# main.net
KiCad netlist of a schematic drawn in Altium Designer
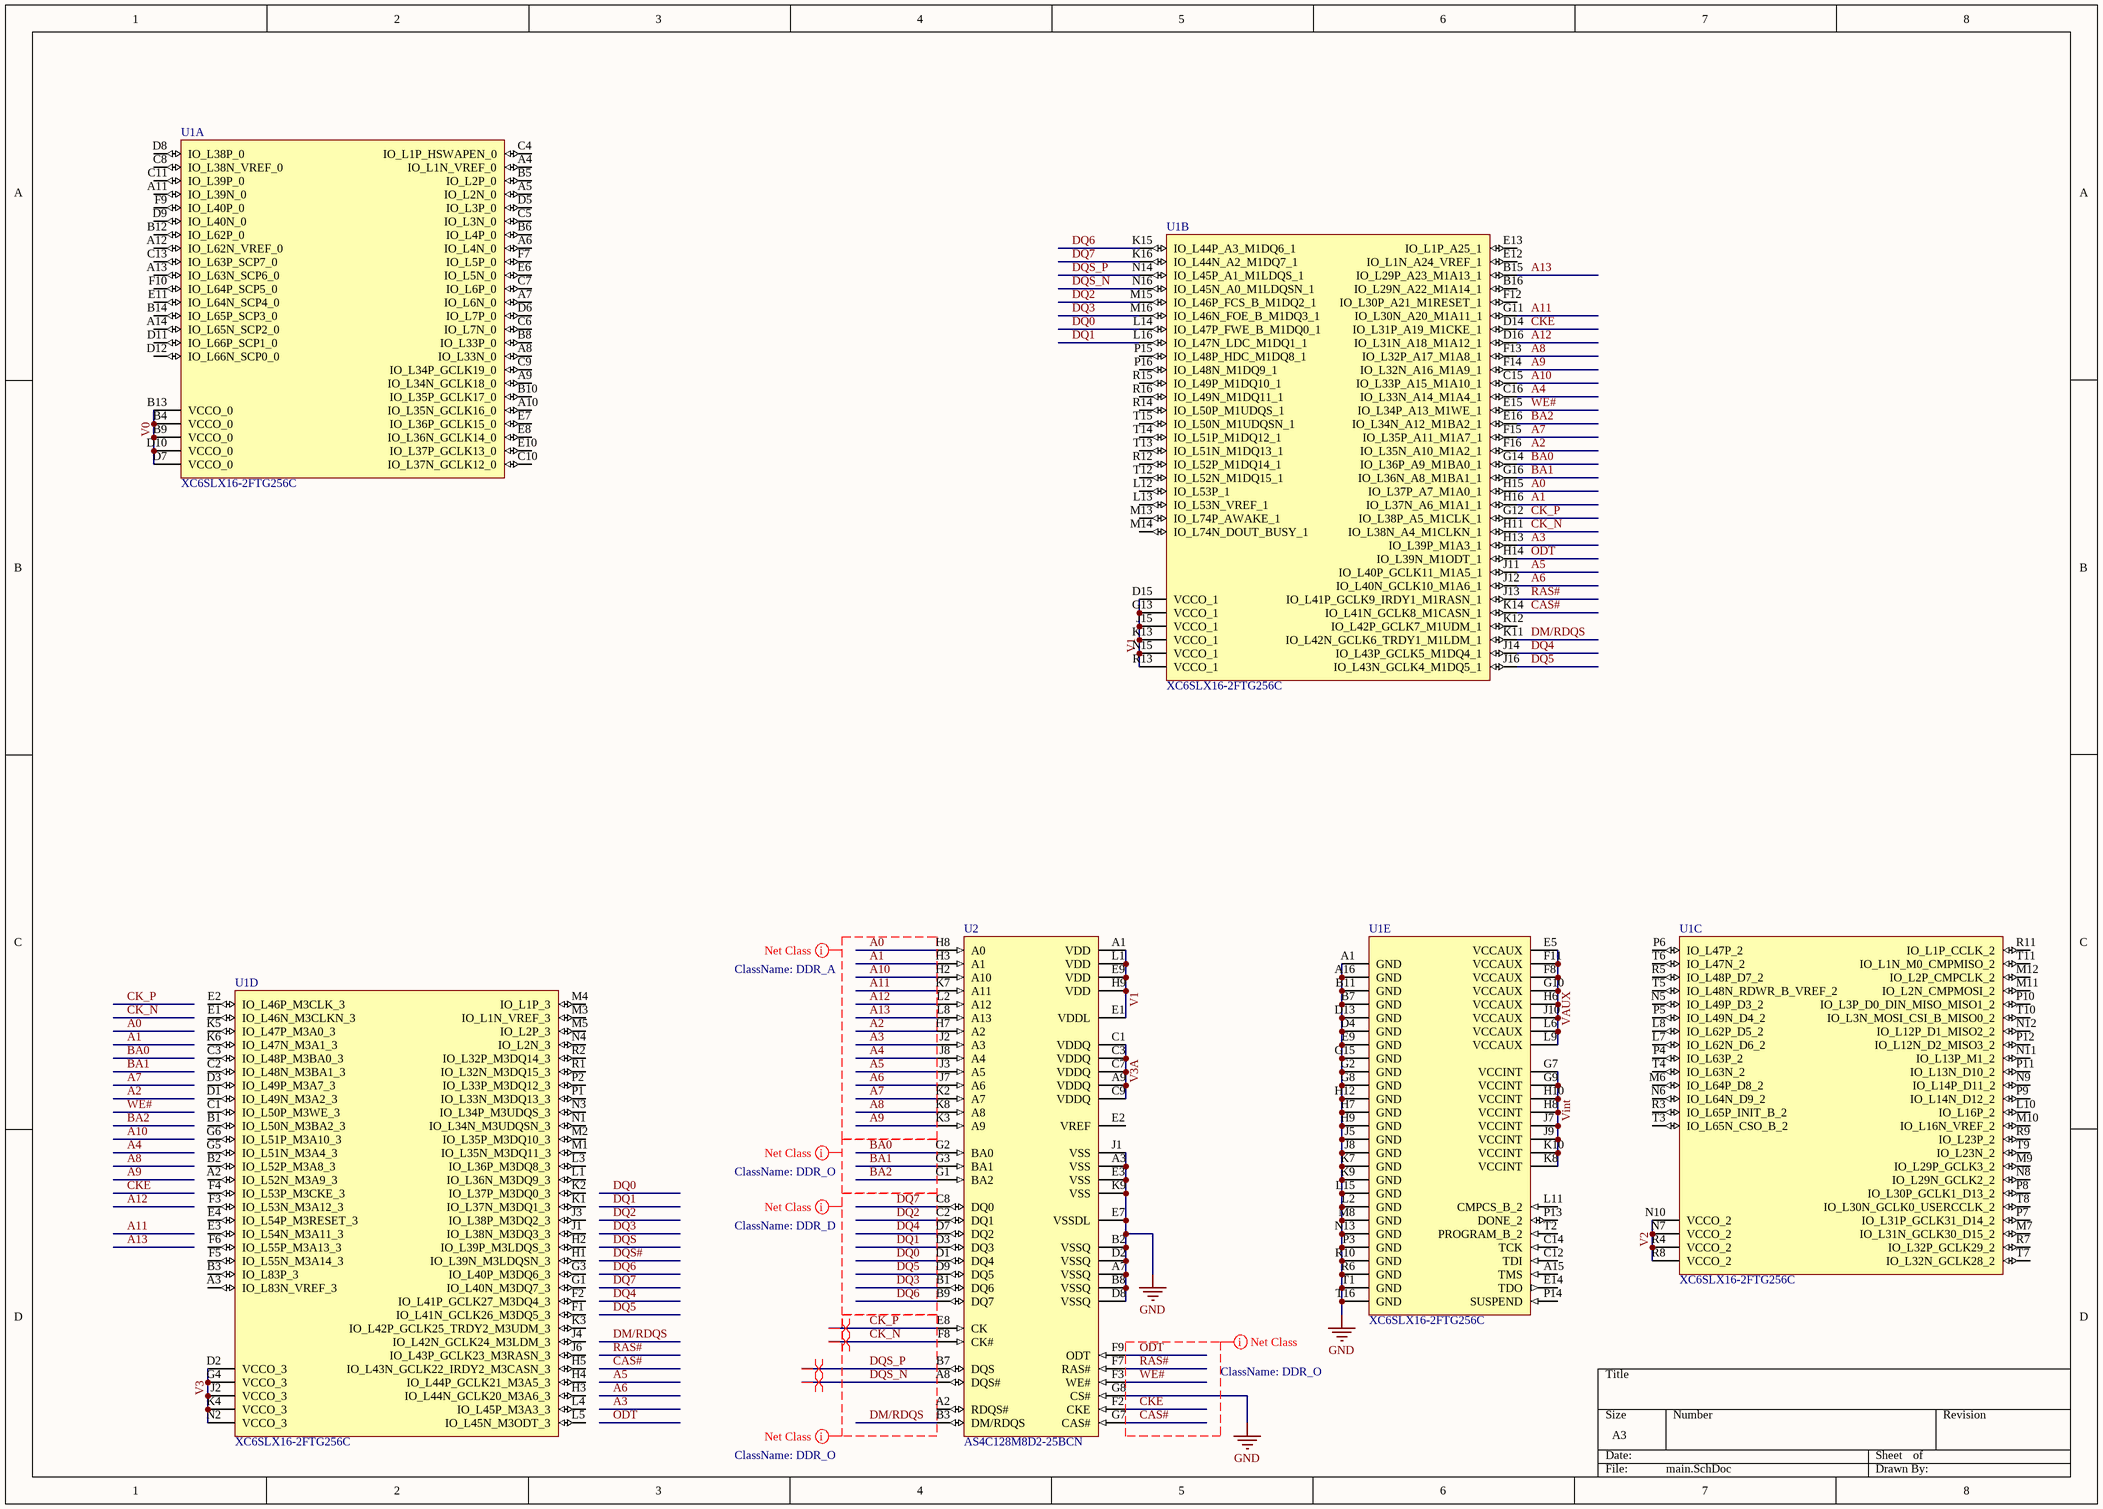
[diagram p0: main.SchDoc]

(export (version "E")
  (design (tool "Eeschema 10.0.6"))
  (components
    (comp (ref "U1")
      (value "XC6SLX16-2FTG256C")
      (footprint "Xilinx_FT256")
      (libsource (lib "niceCircuits") (part "XC6SLX16-2FTG256C"))
    )
    (comp (ref "U2")
      (value "AS4C128M8D2-25BCN")
      (footprint "Alliance_FBGA60")
      (libsource (lib "niceCircuits") (part "AS4C128M8D2-25BCN"))
    )
  )
  (nets
    (net (code "1") (name "/A0") (class "Default")
      (node (ref "U1") (pin "H15") (pinfunction "IO_L37P_A7_M1A0_1_H15") (pintype "bidirectional"))
      (node (ref "U2") (pin "H8") (pinfunction "A0_H8") (pintype "input"))
    )
    (net (code "2") (name "/A1") (class "Default")
      (node (ref "U1") (pin "H16") (pinfunction "IO_L37N_A6_M1A1_1_H16") (pintype "bidirectional"))
      (node (ref "U2") (pin "H3") (pinfunction "A1_H3") (pintype "input"))
    )
    (net (code "3") (name "/A2") (class "Default")
      (node (ref "U1") (pin "F16") (pinfunction "IO_L35N_A10_M1A2_1_F16") (pintype "bidirectional"))
      (node (ref "U2") (pin "H7") (pinfunction "A2_H7") (pintype "input"))
    )
    (net (code "4") (name "/A3") (class "Default")
      (node (ref "U1") (pin "H13") (pinfunction "IO_L39P_M1A3_1_H13") (pintype "bidirectional"))
      (node (ref "U2") (pin "J2") (pinfunction "A3_J2") (pintype "input"))
    )
    (net (code "5") (name "/A4") (class "Default")
      (node (ref "U1") (pin "C16") (pinfunction "IO_L33N_A14_M1A4_1_C16") (pintype "bidirectional"))
      (node (ref "U2") (pin "J8") (pinfunction "A4_J8") (pintype "input"))
    )
    (net (code "6") (name "/A5") (class "Default")
      (node (ref "U1") (pin "J11") (pinfunction "IO_L40P_GCLK11_M1A5_1_J11") (pintype "bidirectional"))
      (node (ref "U2") (pin "J3") (pinfunction "A5_J3") (pintype "input"))
    )
    (net (code "7") (name "/A6") (class "Default")
      (node (ref "U1") (pin "J12") (pinfunction "IO_L40N_GCLK10_M1A6_1_J12") (pintype "bidirectional"))
      (node (ref "U2") (pin "J7") (pinfunction "A6_J7") (pintype "input"))
    )
    (net (code "8") (name "/A7") (class "Default")
      (node (ref "U1") (pin "F15") (pinfunction "IO_L35P_A11_M1A7_1_F15") (pintype "bidirectional"))
      (node (ref "U2") (pin "K2") (pinfunction "A7_K2") (pintype "input"))
    )
    (net (code "9") (name "/A8") (class "Default")
      (node (ref "U1") (pin "F13") (pinfunction "IO_L32P_A17_M1A8_1_F13") (pintype "bidirectional"))
      (node (ref "U2") (pin "K8") (pinfunction "A8_K8") (pintype "input"))
    )
    (net (code "10") (name "/A9") (class "Default")
      (node (ref "U1") (pin "F14") (pinfunction "IO_L32N_A16_M1A9_1_F14") (pintype "bidirectional"))
      (node (ref "U2") (pin "K3") (pinfunction "A9_K3") (pintype "input"))
    )
    (net (code "11") (name "/A10") (class "Default")
      (node (ref "U1") (pin "C15") (pinfunction "IO_L33P_A15_M1A10_1_C15") (pintype "bidirectional"))
      (node (ref "U2") (pin "H2") (pinfunction "A10_H2") (pintype "input"))
    )
    (net (code "12") (name "/A11") (class "Default")
      (node (ref "U1") (pin "G11") (pinfunction "IO_L30N_A20_M1A11_1_G11") (pintype "bidirectional"))
      (node (ref "U2") (pin "K7") (pinfunction "A11_K7") (pintype "input"))
    )
    (net (code "13") (name "/A12") (class "Default")
      (node (ref "U1") (pin "D16") (pinfunction "IO_L31N_A18_M1A12_1_D16") (pintype "bidirectional"))
      (node (ref "U2") (pin "L2") (pinfunction "A12_L2") (pintype "input"))
    )
    (net (code "14") (name "/A13") (class "Default")
      (node (ref "U1") (pin "B15") (pinfunction "IO_L29P_A23_M1A13_1_B15") (pintype "bidirectional"))
      (node (ref "U2") (pin "L8") (pinfunction "A13_L8") (pintype "input"))
    )
    (net (code "15") (name "/BA0") (class "Default")
      (node (ref "U1") (pin "G14") (pinfunction "IO_L36P_A9_M1BA0_1_G14") (pintype "bidirectional"))
      (node (ref "U2") (pin "G2") (pinfunction "BA0_G2") (pintype "input"))
    )
    (net (code "16") (name "/BA1") (class "Default")
      (node (ref "U1") (pin "G16") (pinfunction "IO_L36N_A8_M1BA1_1_G16") (pintype "bidirectional"))
      (node (ref "U2") (pin "G3") (pinfunction "BA1_G3") (pintype "input"))
    )
    (net (code "17") (name "/BA2") (class "Default")
      (node (ref "U1") (pin "E16") (pinfunction "IO_L34N_A12_M1BA2_1_E16") (pintype "bidirectional"))
      (node (ref "U2") (pin "G1") (pinfunction "BA2_G1") (pintype "input"))
    )
    (net (code "18") (name "/CAS#") (class "Default")
      (node (ref "U1") (pin "K14") (pinfunction "IO_L41N_GCLK8_M1CASN_1_K14") (pintype "bidirectional"))
      (node (ref "U2") (pin "G7") (pinfunction "CAS#_G7") (pintype "input"))
    )
    (net (code "19") (name "/CKE") (class "Default")
      (node (ref "U1") (pin "D14") (pinfunction "IO_L31P_A19_M1CKE_1_D14") (pintype "bidirectional"))
      (node (ref "U2") (pin "F2") (pinfunction "CKE_F2") (pintype "input"))
    )
    (net (code "20") (name "/CK_N") (class "Default")
      (node (ref "U1") (pin "H11") (pinfunction "IO_L38N_A4_M1CLKN_1_H11") (pintype "bidirectional"))
      (node (ref "U2") (pin "F8") (pinfunction "CK#_F8") (pintype "input"))
    )
    (net (code "21") (name "/CK_P") (class "Default")
      (node (ref "U1") (pin "G12") (pinfunction "IO_L38P_A5_M1CLK_1_G12") (pintype "bidirectional"))
      (node (ref "U2") (pin "E8") (pinfunction "CK_E8") (pintype "input"))
    )
    (net (code "22") (name "/DM{slash}RDQS") (class "Default")
      (node (ref "U1") (pin "K11") (pinfunction "IO_L42N_GCLK6_TRDY1_M1LDM_1_K11") (pintype "bidirectional"))
      (node (ref "U2") (pin "B3") (pinfunction "DM/RDQS_B3") (pintype "bidirectional"))
    )
    (net (code "23") (name "/DQ0") (class "Default")
      (node (ref "U1") (pin "L14") (pinfunction "IO_L47P_FWE_B_M1DQ0_1_L14") (pintype "bidirectional"))
      (node (ref "U2") (pin "D1") (pinfunction "DQ4_D1") (pintype "bidirectional"))
    )
    (net (code "24") (name "/DQ1") (class "Default")
      (node (ref "U1") (pin "L16") (pinfunction "IO_L47N_LDC_M1DQ1_1_L16") (pintype "bidirectional"))
      (node (ref "U2") (pin "D3") (pinfunction "DQ3_D3") (pintype "bidirectional"))
    )
    (net (code "25") (name "/DQ2") (class "Default")
      (node (ref "U1") (pin "M15") (pinfunction "IO_L46P_FCS_B_M1DQ2_1_M15") (pintype "bidirectional"))
      (node (ref "U2") (pin "C2") (pinfunction "DQ1_C2") (pintype "bidirectional"))
    )
    (net (code "26") (name "/DQ3") (class "Default")
      (node (ref "U1") (pin "M16") (pinfunction "IO_L46N_FOE_B_M1DQ3_1_M16") (pintype "bidirectional"))
      (node (ref "U2") (pin "B1") (pinfunction "DQ6_B1") (pintype "bidirectional"))
    )
    (net (code "27") (name "/DQ4") (class "Default")
      (node (ref "U1") (pin "J14") (pinfunction "IO_L43P_GCLK5_M1DQ4_1_J14") (pintype "bidirectional"))
      (node (ref "U2") (pin "D7") (pinfunction "DQ2_D7") (pintype "bidirectional"))
    )
    (net (code "28") (name "/DQ5") (class "Default")
      (node (ref "U1") (pin "J16") (pinfunction "IO_L43N_GCLK4_M1DQ5_1_J16") (pintype "bidirectional"))
      (node (ref "U2") (pin "D9") (pinfunction "DQ5_D9") (pintype "bidirectional"))
    )
    (net (code "29") (name "/DQ6") (class "Default")
      (node (ref "U1") (pin "K15") (pinfunction "IO_L44P_A3_M1DQ6_1_K15") (pintype "bidirectional"))
      (node (ref "U2") (pin "B9") (pinfunction "DQ7_B9") (pintype "bidirectional"))
    )
    (net (code "30") (name "/DQ7") (class "Default")
      (node (ref "U1") (pin "K16") (pinfunction "IO_L44N_A2_M1DQ7_1_K16") (pintype "bidirectional"))
      (node (ref "U2") (pin "C8") (pinfunction "DQ0_C8") (pintype "bidirectional"))
    )
    (net (code "33") (name "/DQS_N") (class "Default")
      (node (ref "U1") (pin "N16") (pinfunction "IO_L45N_A0_M1LDQSN_1_N16") (pintype "bidirectional"))
      (node (ref "U2") (pin "A8") (pinfunction "DQS#_A8") (pintype "bidirectional"))
    )
    (net (code "34") (name "/DQS_P") (class "Default")
      (node (ref "U1") (pin "N14") (pinfunction "IO_L45P_A1_M1LDQS_1_N14") (pintype "bidirectional"))
      (node (ref "U2") (pin "B7") (pinfunction "DQS_B7") (pintype "bidirectional"))
    )
    (net (code "35") (name "/ODT") (class "Default")
      (node (ref "U1") (pin "H14") (pinfunction "IO_L39N_M1ODT_1_H14") (pintype "bidirectional"))
      (node (ref "U2") (pin "F9") (pinfunction "ODT_F9") (pintype "input"))
    )
    (net (code "36") (name "/RAS#") (class "Default")
      (node (ref "U1") (pin "J13") (pinfunction "IO_L41P_GCLK9_IRDY1_M1RASN_1_J13") (pintype "bidirectional"))
      (node (ref "U2") (pin "F7") (pinfunction "RAS#_F7") (pintype "input"))
    )
    (net (code "37") (name "/V0") (class "Default")
      (node (ref "U1") (pin "B13") (pinfunction "VCCO_0_B13") (pintype "power_in"))
      (node (ref "U1") (pin "B4") (pinfunction "VCCO_0_B4") (pintype "power_in"))
      (node (ref "U1") (pin "B9") (pinfunction "VCCO_0_B9") (pintype "power_in"))
      (node (ref "U1") (pin "D10") (pinfunction "VCCO_0_D10") (pintype "power_in"))
      (node (ref "U1") (pin "D7") (pinfunction "VCCO_0_D7") (pintype "power_in"))
    )
    (net (code "38") (name "/V1") (class "Default")
      (node (ref "U1") (pin "D15") (pinfunction "VCCO_1_D15") (pintype "power_in"))
      (node (ref "U1") (pin "G13") (pinfunction "VCCO_1_G13") (pintype "power_in"))
      (node (ref "U1") (pin "J15") (pinfunction "VCCO_1_J15") (pintype "power_in"))
      (node (ref "U1") (pin "K13") (pinfunction "VCCO_1_K13") (pintype "power_in"))
      (node (ref "U1") (pin "N15") (pinfunction "VCCO_1_N15") (pintype "power_in"))
      (node (ref "U1") (pin "R13") (pinfunction "VCCO_1_R13") (pintype "power_in"))
      (node (ref "U2") (pin "A1") (pinfunction "VDD_A1") (pintype "power_in"))
      (node (ref "U2") (pin "E1") (pinfunction "VDDL_E1") (pintype "power_in"))
      (node (ref "U2") (pin "E9") (pinfunction "VDD_E9") (pintype "power_in"))
      (node (ref "U2") (pin "H9") (pinfunction "VDD_H9") (pintype "power_in"))
      (node (ref "U2") (pin "L1") (pinfunction "VDD_L1") (pintype "power_in"))
    )
    (net (code "39") (name "/V2") (class "Default")
      (node (ref "U1") (pin "N10") (pinfunction "VCCO_2_N10") (pintype "power_in"))
      (node (ref "U1") (pin "N7") (pinfunction "VCCO_2_N7") (pintype "power_in"))
      (node (ref "U1") (pin "R4") (pinfunction "VCCO_2_R4") (pintype "power_in"))
      (node (ref "U1") (pin "R8") (pinfunction "VCCO_2_R8") (pintype "power_in"))
    )
    (net (code "40") (name "/V3") (class "Default")
      (node (ref "U1") (pin "D2") (pinfunction "VCCO_3_D2") (pintype "power_in"))
      (node (ref "U1") (pin "G4") (pinfunction "VCCO_3_G4") (pintype "power_in"))
      (node (ref "U1") (pin "J2") (pinfunction "VCCO_3_J2") (pintype "power_in"))
      (node (ref "U1") (pin "K4") (pinfunction "VCCO_3_K4") (pintype "power_in"))
      (node (ref "U1") (pin "N2") (pinfunction "VCCO_3_N2") (pintype "power_in"))
    )
    (net (code "41") (name "/V3A") (class "Default")
      (node (ref "U2") (pin "A9") (pinfunction "VDDQ_A9") (pintype "power_in"))
      (node (ref "U2") (pin "C1") (pinfunction "VDDQ_C1") (pintype "power_in"))
      (node (ref "U2") (pin "C3") (pinfunction "VDDQ_C3") (pintype "power_in"))
      (node (ref "U2") (pin "C7") (pinfunction "VDDQ_C7") (pintype "power_in"))
      (node (ref "U2") (pin "C9") (pinfunction "VDDQ_C9") (pintype "power_in"))
    )
    (net (code "42") (name "/VAUX") (class "Default")
      (node (ref "U1") (pin "E5") (pinfunction "VCCAUX_E5") (pintype "power_in"))
      (node (ref "U1") (pin "F11") (pinfunction "VCCAUX_F11") (pintype "power_in"))
      (node (ref "U1") (pin "F8") (pinfunction "VCCAUX_F8") (pintype "power_in"))
      (node (ref "U1") (pin "G10") (pinfunction "VCCAUX_G10") (pintype "power_in"))
      (node (ref "U1") (pin "H6") (pinfunction "VCCAUX_H6") (pintype "power_in"))
      (node (ref "U1") (pin "J10") (pinfunction "VCCAUX_J10") (pintype "power_in"))
      (node (ref "U1") (pin "L6") (pinfunction "VCCAUX_L6") (pintype "power_in"))
      (node (ref "U1") (pin "L9") (pinfunction "VCCAUX_L9") (pintype "power_in"))
    )
    (net (code "43") (name "/Vint") (class "Default")
      (node (ref "U1") (pin "G7") (pinfunction "VCCINT_G7") (pintype "power_in"))
      (node (ref "U1") (pin "G9") (pinfunction "VCCINT_G9") (pintype "power_in"))
      (node (ref "U1") (pin "H10") (pinfunction "VCCINT_H10") (pintype "power_in"))
      (node (ref "U1") (pin "H8") (pinfunction "VCCINT_H8") (pintype "power_in"))
      (node (ref "U1") (pin "J7") (pinfunction "VCCINT_J7") (pintype "power_in"))
      (node (ref "U1") (pin "J9") (pinfunction "VCCINT_J9") (pintype "power_in"))
      (node (ref "U1") (pin "K10") (pinfunction "VCCINT_K10") (pintype "power_in"))
      (node (ref "U1") (pin "K8") (pinfunction "VCCINT_K8") (pintype "power_in"))
    )
    (net (code "44") (name "/WE#") (class "Default")
      (node (ref "U1") (pin "E15") (pinfunction "IO_L34P_A13_M1WE_1_E15") (pintype "bidirectional"))
      (node (ref "U2") (pin "F3") (pinfunction "WE#_F3") (pintype "input"))
    )
    (net (code "45") (name "GND") (class "Default")
      (node (ref "U1") (pin "A1") (pinfunction "GND_A1") (pintype "power_in"))
      (node (ref "U1") (pin "A16") (pinfunction "GND_A16") (pintype "power_in"))
      (node (ref "U1") (pin "B11") (pinfunction "GND_B11") (pintype "power_in"))
      (node (ref "U1") (pin "B7") (pinfunction "GND_B7") (pintype "power_in"))
      (node (ref "U1") (pin "D13") (pinfunction "GND_D13") (pintype "power_in"))
      (node (ref "U1") (pin "D4") (pinfunction "GND_D4") (pintype "power_in"))
      (node (ref "U1") (pin "E9") (pinfunction "GND_E9") (pintype "power_in"))
      (node (ref "U1") (pin "G15") (pinfunction "GND_G15") (pintype "power_in"))
      (node (ref "U1") (pin "G2") (pinfunction "GND_G2") (pintype "power_in"))
      (node (ref "U1") (pin "G8") (pinfunction "GND_G8") (pintype "power_in"))
      (node (ref "U1") (pin "H12") (pinfunction "GND_H12") (pintype "power_in"))
      (node (ref "U1") (pin "H7") (pinfunction "GND_H7") (pintype "power_in"))
      (node (ref "U1") (pin "H9") (pinfunction "GND_H9") (pintype "power_in"))
      (node (ref "U1") (pin "J5") (pinfunction "GND_J5") (pintype "power_in"))
      (node (ref "U1") (pin "J8") (pinfunction "GND_J8") (pintype "power_in"))
      (node (ref "U1") (pin "K7") (pinfunction "GND_K7") (pintype "power_in"))
      (node (ref "U1") (pin "K9") (pinfunction "GND_K9") (pintype "power_in"))
      (node (ref "U1") (pin "L15") (pinfunction "GND_L15") (pintype "power_in"))
      (node (ref "U1") (pin "L2") (pinfunction "GND_L2") (pintype "power_in"))
      (node (ref "U1") (pin "M8") (pinfunction "GND_M8") (pintype "power_in"))
      (node (ref "U1") (pin "N13") (pinfunction "GND_N13") (pintype "power_in"))
      (node (ref "U1") (pin "P3") (pinfunction "GND_P3") (pintype "power_in"))
      (node (ref "U1") (pin "R10") (pinfunction "GND_R10") (pintype "power_in"))
      (node (ref "U1") (pin "R6") (pinfunction "GND_R6") (pintype "power_in"))
      (node (ref "U1") (pin "T1") (pinfunction "GND_T1") (pintype "power_in"))
      (node (ref "U1") (pin "T16") (pinfunction "GND_T16") (pintype "power_in"))
      (node (ref "U2") (pin "A3") (pinfunction "VSS_A3") (pintype "power_in"))
      (node (ref "U2") (pin "A7") (pinfunction "VSSQ_A7") (pintype "power_in"))
      (node (ref "U2") (pin "B2") (pinfunction "VSSQ_B2") (pintype "power_in"))
      (node (ref "U2") (pin "B8") (pinfunction "VSSQ_B8") (pintype "power_in"))
      (node (ref "U2") (pin "D2") (pinfunction "VSSQ_D2") (pintype "power_in"))
      (node (ref "U2") (pin "D8") (pinfunction "VSSQ_D8") (pintype "power_in"))
      (node (ref "U2") (pin "E3") (pinfunction "VSS_E3") (pintype "power_in"))
      (node (ref "U2") (pin "E7") (pinfunction "VSSDL_E7") (pintype "power_in"))
      (node (ref "U2") (pin "G8") (pinfunction "CS#_G8") (pintype "input"))
      (node (ref "U2") (pin "J1") (pinfunction "VSS_J1") (pintype "power_in"))
      (node (ref "U2") (pin "K9") (pinfunction "VSS_K9") (pintype "power_in"))
    )
    (net (code "46") (name "unconnected-(U1A-IO_L1N_VREF_0-PadA4)") (class "Default")
      (node (ref "U1") (pin "A4") (pinfunction "IO_L1N_VREF_0_A4") (pintype "bidirectional"))
    )
    (net (code "47") (name "unconnected-(U1A-IO_L1P_HSWAPEN_0-PadC4)") (class "Default")
      (node (ref "U1") (pin "C4") (pinfunction "IO_L1P_HSWAPEN_0_C4") (pintype "bidirectional"))
    )
    (net (code "48") (name "unconnected-(U1A-IO_L2N_0-PadA5)") (class "Default")
      (node (ref "U1") (pin "A5") (pinfunction "IO_L2N_0_A5") (pintype "bidirectional"))
    )
    (net (code "49") (name "unconnected-(U1A-IO_L2P_0-PadB5)") (class "Default")
      (node (ref "U1") (pin "B5") (pinfunction "IO_L2P_0_B5") (pintype "bidirectional"))
    )
    (net (code "50") (name "unconnected-(U1A-IO_L3N_0-PadC5)") (class "Default")
      (node (ref "U1") (pin "C5") (pinfunction "IO_L3N_0_C5") (pintype "bidirectional"))
    )
    (net (code "51") (name "unconnected-(U1A-IO_L3P_0-PadD5)") (class "Default")
      (node (ref "U1") (pin "D5") (pinfunction "IO_L3P_0_D5") (pintype "bidirectional"))
    )
    (net (code "52") (name "unconnected-(U1A-IO_L4N_0-PadA6)") (class "Default")
      (node (ref "U1") (pin "A6") (pinfunction "IO_L4N_0_A6") (pintype "bidirectional"))
    )
    (net (code "53") (name "unconnected-(U1A-IO_L4P_0-PadB6)") (class "Default")
      (node (ref "U1") (pin "B6") (pinfunction "IO_L4P_0_B6") (pintype "bidirectional"))
    )
    (net (code "54") (name "unconnected-(U1A-IO_L5N_0-PadE6)") (class "Default")
      (node (ref "U1") (pin "E6") (pinfunction "IO_L5N_0_E6") (pintype "bidirectional"))
    )
    (net (code "55") (name "unconnected-(U1A-IO_L5P_0-PadF7)") (class "Default")
      (node (ref "U1") (pin "F7") (pinfunction "IO_L5P_0_F7") (pintype "bidirectional"))
    )
    (net (code "56") (name "unconnected-(U1A-IO_L6N_0-PadA7)") (class "Default")
      (node (ref "U1") (pin "A7") (pinfunction "IO_L6N_0_A7") (pintype "bidirectional"))
    )
    (net (code "57") (name "unconnected-(U1A-IO_L6P_0-PadC7)") (class "Default")
      (node (ref "U1") (pin "C7") (pinfunction "IO_L6P_0_C7") (pintype "bidirectional"))
    )
    (net (code "58") (name "unconnected-(U1A-IO_L7N_0-PadC6)") (class "Default")
      (node (ref "U1") (pin "C6") (pinfunction "IO_L7N_0_C6") (pintype "bidirectional"))
    )
    (net (code "59") (name "unconnected-(U1A-IO_L7P_0-PadD6)") (class "Default")
      (node (ref "U1") (pin "D6") (pinfunction "IO_L7P_0_D6") (pintype "bidirectional"))
    )
    (net (code "60") (name "unconnected-(U1A-IO_L33N_0-PadA8)") (class "Default")
      (node (ref "U1") (pin "A8") (pinfunction "IO_L33N_0_A8") (pintype "bidirectional"))
    )
    (net (code "61") (name "unconnected-(U1A-IO_L33P_0-PadB8)") (class "Default")
      (node (ref "U1") (pin "B8") (pinfunction "IO_L33P_0_B8") (pintype "bidirectional"))
    )
    (net (code "62") (name "unconnected-(U1A-IO_L34N_GCLK18_0-PadA9)") (class "Default")
      (node (ref "U1") (pin "A9") (pinfunction "IO_L34N_GCLK18_0_A9") (pintype "bidirectional"))
    )
    (net (code "63") (name "unconnected-(U1A-IO_L34P_GCLK19_0-PadC9)") (class "Default")
      (node (ref "U1") (pin "C9") (pinfunction "IO_L34P_GCLK19_0_C9") (pintype "bidirectional"))
    )
    (net (code "64") (name "unconnected-(U1A-IO_L35N_GCLK16_0-PadA10)") (class "Default")
      (node (ref "U1") (pin "A10") (pinfunction "IO_L35N_GCLK16_0_A10") (pintype "bidirectional"))
    )
    (net (code "65") (name "unconnected-(U1A-IO_L35P_GCLK17_0-PadB10)") (class "Default")
      (node (ref "U1") (pin "B10") (pinfunction "IO_L35P_GCLK17_0_B10") (pintype "bidirectional"))
    )
    (net (code "66") (name "unconnected-(U1A-IO_L36N_GCLK14_0-PadE8)") (class "Default")
      (node (ref "U1") (pin "E8") (pinfunction "IO_L36N_GCLK14_0_E8") (pintype "bidirectional"))
    )
    (net (code "67") (name "unconnected-(U1A-IO_L36P_GCLK15_0-PadE7)") (class "Default")
      (node (ref "U1") (pin "E7") (pinfunction "IO_L36P_GCLK15_0_E7") (pintype "bidirectional"))
    )
    (net (code "68") (name "unconnected-(U1A-IO_L37N_GCLK12_0-PadC10)") (class "Default")
      (node (ref "U1") (pin "C10") (pinfunction "IO_L37N_GCLK12_0_C10") (pintype "bidirectional"))
    )
    (net (code "69") (name "unconnected-(U1A-IO_L37P_GCLK13_0-PadE10)") (class "Default")
      (node (ref "U1") (pin "E10") (pinfunction "IO_L37P_GCLK13_0_E10") (pintype "bidirectional"))
    )
    (net (code "70") (name "unconnected-(U1A-IO_L38N_VREF_0-PadC8)") (class "Default")
      (node (ref "U1") (pin "C8") (pinfunction "IO_L38N_VREF_0_C8") (pintype "bidirectional"))
    )
    (net (code "71") (name "unconnected-(U1A-IO_L38P_0-PadD8)") (class "Default")
      (node (ref "U1") (pin "D8") (pinfunction "IO_L38P_0_D8") (pintype "bidirectional"))
    )
    (net (code "72") (name "unconnected-(U1A-IO_L39N_0-PadA11)") (class "Default")
      (node (ref "U1") (pin "A11") (pinfunction "IO_L39N_0_A11") (pintype "bidirectional"))
    )
    (net (code "73") (name "unconnected-(U1A-IO_L39P_0-PadC11)") (class "Default")
      (node (ref "U1") (pin "C11") (pinfunction "IO_L39P_0_C11") (pintype "bidirectional"))
    )
    (net (code "74") (name "unconnected-(U1A-IO_L40N_0-PadD9)") (class "Default")
      (node (ref "U1") (pin "D9") (pinfunction "IO_L40N_0_D9") (pintype "bidirectional"))
    )
    (net (code "75") (name "unconnected-(U1A-IO_L40P_0-PadF9)") (class "Default")
      (node (ref "U1") (pin "F9") (pinfunction "IO_L40P_0_F9") (pintype "bidirectional"))
    )
    (net (code "76") (name "unconnected-(U1A-IO_L62N_VREF_0-PadA12)") (class "Default")
      (node (ref "U1") (pin "A12") (pinfunction "IO_L62N_VREF_0_A12") (pintype "bidirectional"))
    )
    (net (code "77") (name "unconnected-(U1A-IO_L62P_0-PadB12)") (class "Default")
      (node (ref "U1") (pin "B12") (pinfunction "IO_L62P_0_B12") (pintype "bidirectional"))
    )
    (net (code "78") (name "unconnected-(U1A-IO_L63N_SCP6_0-PadA13)") (class "Default")
      (node (ref "U1") (pin "A13") (pinfunction "IO_L63N_SCP6_0_A13") (pintype "bidirectional"))
    )
    (net (code "79") (name "unconnected-(U1A-IO_L63P_SCP7_0-PadC13)") (class "Default")
      (node (ref "U1") (pin "C13") (pinfunction "IO_L63P_SCP7_0_C13") (pintype "bidirectional"))
    )
    (net (code "80") (name "unconnected-(U1A-IO_L64N_SCP4_0-PadE11)") (class "Default")
      (node (ref "U1") (pin "E11") (pinfunction "IO_L64N_SCP4_0_E11") (pintype "bidirectional"))
    )
    (net (code "81") (name "unconnected-(U1A-IO_L64P_SCP5_0-PadF10)") (class "Default")
      (node (ref "U1") (pin "F10") (pinfunction "IO_L64P_SCP5_0_F10") (pintype "bidirectional"))
    )
    (net (code "82") (name "unconnected-(U1A-IO_L65N_SCP2_0-PadA14)") (class "Default")
      (node (ref "U1") (pin "A14") (pinfunction "IO_L65N_SCP2_0_A14") (pintype "bidirectional"))
    )
    (net (code "83") (name "unconnected-(U1A-IO_L65P_SCP3_0-PadB14)") (class "Default")
      (node (ref "U1") (pin "B14") (pinfunction "IO_L65P_SCP3_0_B14") (pintype "bidirectional"))
    )
    (net (code "84") (name "unconnected-(U1A-IO_L66N_SCP0_0-PadD12)") (class "Default")
      (node (ref "U1") (pin "D12") (pinfunction "IO_L66N_SCP0_0_D12") (pintype "bidirectional"))
    )
    (net (code "85") (name "unconnected-(U1A-IO_L66P_SCP1_0-PadD11)") (class "Default")
      (node (ref "U1") (pin "D11") (pinfunction "IO_L66P_SCP1_0_D11") (pintype "bidirectional"))
    )
    (net (code "86") (name "unconnected-(U1B-IO_L1N_A24_VREF_1-PadE12)") (class "Default")
      (node (ref "U1") (pin "E12") (pinfunction "IO_L1N_A24_VREF_1_E12") (pintype "bidirectional"))
    )
    (net (code "87") (name "unconnected-(U1B-IO_L1P_A25_1-PadE13)") (class "Default")
      (node (ref "U1") (pin "E13") (pinfunction "IO_L1P_A25_1_E13") (pintype "bidirectional"))
    )
    (net (code "88") (name "unconnected-(U1B-IO_L29N_A22_M1A14_1-PadB16)") (class "Default")
      (node (ref "U1") (pin "B16") (pinfunction "IO_L29N_A22_M1A14_1_B16") (pintype "bidirectional"))
    )
    (net (code "89") (name "unconnected-(U1B-IO_L30P_A21_M1RESET_1-PadF12)") (class "Default")
      (node (ref "U1") (pin "F12") (pinfunction "IO_L30P_A21_M1RESET_1_F12") (pintype "bidirectional"))
    )
    (net (code "90") (name "unconnected-(U1B-IO_L42P_GCLK7_M1UDM_1-PadK12)") (class "Default")
      (node (ref "U1") (pin "K12") (pinfunction "IO_L42P_GCLK7_M1UDM_1_K12") (pintype "bidirectional"))
    )
    (net (code "91") (name "unconnected-(U1B-IO_L48N_M1DQ9_1-PadP16)") (class "Default")
      (node (ref "U1") (pin "P16") (pinfunction "IO_L48N_M1DQ9_1_P16") (pintype "bidirectional"))
    )
    (net (code "92") (name "unconnected-(U1B-IO_L48P_HDC_M1DQ8_1-PadP15)") (class "Default")
      (node (ref "U1") (pin "P15") (pinfunction "IO_L48P_HDC_M1DQ8_1_P15") (pintype "bidirectional"))
    )
    (net (code "93") (name "unconnected-(U1B-IO_L49N_M1DQ11_1-PadR16)") (class "Default")
      (node (ref "U1") (pin "R16") (pinfunction "IO_L49N_M1DQ11_1_R16") (pintype "bidirectional"))
    )
    (net (code "94") (name "unconnected-(U1B-IO_L49P_M1DQ10_1-PadR15)") (class "Default")
      (node (ref "U1") (pin "R15") (pinfunction "IO_L49P_M1DQ10_1_R15") (pintype "bidirectional"))
    )
    (net (code "95") (name "unconnected-(U1B-IO_L50N_M1UDQSN_1-PadT15)") (class "Default")
      (node (ref "U1") (pin "T15") (pinfunction "IO_L50N_M1UDQSN_1_T15") (pintype "bidirectional"))
    )
    (net (code "96") (name "unconnected-(U1B-IO_L50P_M1UDQS_1-PadR14)") (class "Default")
      (node (ref "U1") (pin "R14") (pinfunction "IO_L50P_M1UDQS_1_R14") (pintype "bidirectional"))
    )
    (net (code "97") (name "unconnected-(U1B-IO_L51N_M1DQ13_1-PadT13)") (class "Default")
      (node (ref "U1") (pin "T13") (pinfunction "IO_L51N_M1DQ13_1_T13") (pintype "bidirectional"))
    )
    (net (code "98") (name "unconnected-(U1B-IO_L51P_M1DQ12_1-PadT14)") (class "Default")
      (node (ref "U1") (pin "T14") (pinfunction "IO_L51P_M1DQ12_1_T14") (pintype "bidirectional"))
    )
    (net (code "99") (name "unconnected-(U1B-IO_L52N_M1DQ15_1-PadT12)") (class "Default")
      (node (ref "U1") (pin "T12") (pinfunction "IO_L52N_M1DQ15_1_T12") (pintype "bidirectional"))
    )
    (net (code "100") (name "unconnected-(U1B-IO_L52P_M1DQ14_1-PadR12)") (class "Default")
      (node (ref "U1") (pin "R12") (pinfunction "IO_L52P_M1DQ14_1_R12") (pintype "bidirectional"))
    )
    (net (code "101") (name "unconnected-(U1B-IO_L53N_VREF_1-PadL13)") (class "Default")
      (node (ref "U1") (pin "L13") (pinfunction "IO_L53N_VREF_1_L13") (pintype "bidirectional"))
    )
    (net (code "102") (name "unconnected-(U1B-IO_L53P_1-PadL12)") (class "Default")
      (node (ref "U1") (pin "L12") (pinfunction "IO_L53P_1_L12") (pintype "bidirectional"))
    )
    (net (code "103") (name "unconnected-(U1B-IO_L74N_DOUT_BUSY_1-PadM14)") (class "Default")
      (node (ref "U1") (pin "M14") (pinfunction "IO_L74N_DOUT_BUSY_1_M14") (pintype "bidirectional"))
    )
    (net (code "104") (name "unconnected-(U1B-IO_L74P_AWAKE_1-PadM13)") (class "Default")
      (node (ref "U1") (pin "M13") (pinfunction "IO_L74P_AWAKE_1_M13") (pintype "bidirectional"))
    )
    (net (code "105") (name "unconnected-(U1C-IO_L1N_M0_CMPMISO_2-PadT11)") (class "Default")
      (node (ref "U1") (pin "T11") (pinfunction "IO_L1N_M0_CMPMISO_2_T11") (pintype "bidirectional"))
    )
    (net (code "106") (name "unconnected-(U1C-IO_L1P_CCLK_2-PadR11)") (class "Default")
      (node (ref "U1") (pin "R11") (pinfunction "IO_L1P_CCLK_2_R11") (pintype "bidirectional"))
    )
    (net (code "107") (name "unconnected-(U1C-IO_L2N_CMPMOSI_2-PadM11)") (class "Default")
      (node (ref "U1") (pin "M11") (pinfunction "IO_L2N_CMPMOSI_2_M11") (pintype "bidirectional"))
    )
    (net (code "108") (name "unconnected-(U1C-IO_L2P_CMPCLK_2-PadM12)") (class "Default")
      (node (ref "U1") (pin "M12") (pinfunction "IO_L2P_CMPCLK_2_M12") (pintype "bidirectional"))
    )
    (net (code "109") (name "unconnected-(U1C-IO_L3N_MOSI_CSI_B_MISO0_2-PadT10)") (class "Default")
      (node (ref "U1") (pin "T10") (pinfunction "IO_L3N_MOSI_CSI_B_MISO0_2_T10") (pintype "bidirectional"))
    )
    (net (code "110") (name "unconnected-(U1C-IO_L3P_D0_DIN_MISO_MISO1_2-PadP10)") (class "Default")
      (node (ref "U1") (pin "P10") (pinfunction "IO_L3P_D0_DIN_MISO_MISO1_2_P10") (pintype "bidirectional"))
    )
    (net (code "111") (name "unconnected-(U1C-IO_L12N_D2_MISO3_2-PadP12)") (class "Default")
      (node (ref "U1") (pin "P12") (pinfunction "IO_L12N_D2_MISO3_2_P12") (pintype "bidirectional"))
    )
    (net (code "112") (name "unconnected-(U1C-IO_L12P_D1_MISO2_2-PadN12)") (class "Default")
      (node (ref "U1") (pin "N12") (pinfunction "IO_L12P_D1_MISO2_2_N12") (pintype "bidirectional"))
    )
    (net (code "113") (name "unconnected-(U1C-IO_L13N_D10_2-PadP11)") (class "Default")
      (node (ref "U1") (pin "P11") (pinfunction "IO_L13N_D10_2_P11") (pintype "bidirectional"))
    )
    (net (code "114") (name "unconnected-(U1C-IO_L13P_M1_2-PadN11)") (class "Default")
      (node (ref "U1") (pin "N11") (pinfunction "IO_L13P_M1_2_N11") (pintype "bidirectional"))
    )
    (net (code "115") (name "unconnected-(U1C-IO_L14N_D12_2-PadP9)") (class "Default")
      (node (ref "U1") (pin "P9") (pinfunction "IO_L14N_D12_2_P9") (pintype "bidirectional"))
    )
    (net (code "116") (name "unconnected-(U1C-IO_L14P_D11_2-PadN9)") (class "Default")
      (node (ref "U1") (pin "N9") (pinfunction "IO_L14P_D11_2_N9") (pintype "bidirectional"))
    )
    (net (code "117") (name "unconnected-(U1C-IO_L16N_VREF_2-PadM10)") (class "Default")
      (node (ref "U1") (pin "M10") (pinfunction "IO_L16N_VREF_2_M10") (pintype "bidirectional"))
    )
    (net (code "118") (name "unconnected-(U1C-IO_L16P_2-PadL10)") (class "Default")
      (node (ref "U1") (pin "L10") (pinfunction "IO_L16P_2_L10") (pintype "bidirectional"))
    )
    (net (code "119") (name "unconnected-(U1C-IO_L23N_2-PadT9)") (class "Default")
      (node (ref "U1") (pin "T9") (pinfunction "IO_L23N_2_T9") (pintype "bidirectional"))
    )
    (net (code "120") (name "unconnected-(U1C-IO_L23P_2-PadR9)") (class "Default")
      (node (ref "U1") (pin "R9") (pinfunction "IO_L23P_2_R9") (pintype "bidirectional"))
    )
    (net (code "121") (name "unconnected-(U1C-IO_L29N_GCLK2_2-PadN8)") (class "Default")
      (node (ref "U1") (pin "N8") (pinfunction "IO_L29N_GCLK2_2_N8") (pintype "bidirectional"))
    )
    (net (code "122") (name "unconnected-(U1C-IO_L29P_GCLK3_2-PadM9)") (class "Default")
      (node (ref "U1") (pin "M9") (pinfunction "IO_L29P_GCLK3_2_M9") (pintype "bidirectional"))
    )
    (net (code "123") (name "unconnected-(U1C-IO_L30N_GCLK0_USERCCLK_2-PadT8)") (class "Default")
      (node (ref "U1") (pin "T8") (pinfunction "IO_L30N_GCLK0_USERCCLK_2_T8") (pintype "bidirectional"))
    )
    (net (code "124") (name "unconnected-(U1C-IO_L30P_GCLK1_D13_2-PadP8)") (class "Default")
      (node (ref "U1") (pin "P8") (pinfunction "IO_L30P_GCLK1_D13_2_P8") (pintype "bidirectional"))
    )
    (net (code "125") (name "unconnected-(U1C-IO_L31N_GCLK30_D15_2-PadM7)") (class "Default")
      (node (ref "U1") (pin "M7") (pinfunction "IO_L31N_GCLK30_D15_2_M7") (pintype "bidirectional"))
    )
    (net (code "126") (name "unconnected-(U1C-IO_L31P_GCLK31_D14_2-PadP7)") (class "Default")
      (node (ref "U1") (pin "P7") (pinfunction "IO_L31P_GCLK31_D14_2_P7") (pintype "bidirectional"))
    )
    (net (code "127") (name "unconnected-(U1C-IO_L32N_GCLK28_2-PadT7)") (class "Default")
      (node (ref "U1") (pin "T7") (pinfunction "IO_L32N_GCLK28_2_T7") (pintype "bidirectional"))
    )
    (net (code "128") (name "unconnected-(U1C-IO_L32P_GCLK29_2-PadR7)") (class "Default")
      (node (ref "U1") (pin "R7") (pinfunction "IO_L32P_GCLK29_2_R7") (pintype "bidirectional"))
    )
    (net (code "129") (name "unconnected-(U1C-IO_L47N_2-PadT6)") (class "Default")
      (node (ref "U1") (pin "T6") (pinfunction "IO_L47N_2_T6") (pintype "bidirectional"))
    )
    (net (code "130") (name "unconnected-(U1C-IO_L47P_2-PadP6)") (class "Default")
      (node (ref "U1") (pin "P6") (pinfunction "IO_L47P_2_P6") (pintype "bidirectional"))
    )
    (net (code "131") (name "unconnected-(U1C-IO_L48N_RDWR_B_VREF_2-PadT5)") (class "Default")
      (node (ref "U1") (pin "T5") (pinfunction "IO_L48N_RDWR_B_VREF_2_T5") (pintype "bidirectional"))
    )
    (net (code "132") (name "unconnected-(U1C-IO_L48P_D7_2-PadR5)") (class "Default")
      (node (ref "U1") (pin "R5") (pinfunction "IO_L48P_D7_2_R5") (pintype "bidirectional"))
    )
    (net (code "133") (name "unconnected-(U1C-IO_L49N_D4_2-PadP5)") (class "Default")
      (node (ref "U1") (pin "P5") (pinfunction "IO_L49N_D4_2_P5") (pintype "bidirectional"))
    )
    (net (code "134") (name "unconnected-(U1C-IO_L49P_D3_2-PadN5)") (class "Default")
      (node (ref "U1") (pin "N5") (pinfunction "IO_L49P_D3_2_N5") (pintype "bidirectional"))
    )
    (net (code "135") (name "unconnected-(U1C-IO_L62N_D6_2-PadL7)") (class "Default")
      (node (ref "U1") (pin "L7") (pinfunction "IO_L62N_D6_2_L7") (pintype "bidirectional"))
    )
    (net (code "136") (name "unconnected-(U1C-IO_L62P_D5_2-PadL8)") (class "Default")
      (node (ref "U1") (pin "L8") (pinfunction "IO_L62P_D5_2_L8") (pintype "bidirectional"))
    )
    (net (code "137") (name "unconnected-(U1C-IO_L63N_2-PadT4)") (class "Default")
      (node (ref "U1") (pin "T4") (pinfunction "IO_L63N_2_T4") (pintype "bidirectional"))
    )
    (net (code "138") (name "unconnected-(U1C-IO_L63P_2-PadP4)") (class "Default")
      (node (ref "U1") (pin "P4") (pinfunction "IO_L63P_2_P4") (pintype "bidirectional"))
    )
    (net (code "139") (name "unconnected-(U1C-IO_L64N_D9_2-PadN6)") (class "Default")
      (node (ref "U1") (pin "N6") (pinfunction "IO_L64N_D9_2_N6") (pintype "bidirectional"))
    )
    (net (code "140") (name "unconnected-(U1C-IO_L64P_D8_2-PadM6)") (class "Default")
      (node (ref "U1") (pin "M6") (pinfunction "IO_L64P_D8_2_M6") (pintype "bidirectional"))
    )
    (net (code "141") (name "unconnected-(U1C-IO_L65N_CSO_B_2-PadT3)") (class "Default")
      (node (ref "U1") (pin "T3") (pinfunction "IO_L65N_CSO_B_2_T3") (pintype "bidirectional"))
    )
    (net (code "142") (name "unconnected-(U1C-IO_L65P_INIT_B_2-PadR3)") (class "Default")
      (node (ref "U1") (pin "R3") (pinfunction "IO_L65P_INIT_B_2_R3") (pintype "bidirectional"))
    )
    (net (code "143") (name "unconnected-(U1D-IO_L1N_VREF_3-PadM3)") (class "Default")
      (node (ref "U1") (pin "M3") (pinfunction "IO_L1N_VREF_3_M3") (pintype "bidirectional"))
    )
    (net (code "144") (name "unconnected-(U1D-IO_L1P_3-PadM4)") (class "Default")
      (node (ref "U1") (pin "M4") (pinfunction "IO_L1P_3_M4") (pintype "bidirectional"))
    )
    (net (code "145") (name "unconnected-(U1D-IO_L2N_3-PadN4)") (class "Default")
      (node (ref "U1") (pin "N4") (pinfunction "IO_L2N_3_N4") (pintype "bidirectional"))
    )
    (net (code "146") (name "unconnected-(U1D-IO_L2P_3-PadM5)") (class "Default")
      (node (ref "U1") (pin "M5") (pinfunction "IO_L2P_3_M5") (pintype "bidirectional"))
    )
    (net (code "147") (name "unconnected-(U1D-IO_L32N_M3DQ15_3-PadR1)") (class "Default")
      (node (ref "U1") (pin "R1") (pinfunction "IO_L32N_M3DQ15_3_R1") (pintype "bidirectional"))
    )
    (net (code "148") (name "unconnected-(U1D-IO_L32P_M3DQ14_3-PadR2)") (class "Default")
      (node (ref "U1") (pin "R2") (pinfunction "IO_L32P_M3DQ14_3_R2") (pintype "bidirectional"))
    )
    (net (code "149") (name "unconnected-(U1D-IO_L33N_M3DQ13_3-PadP1)") (class "Default")
      (node (ref "U1") (pin "P1") (pinfunction "IO_L33N_M3DQ13_3_P1") (pintype "bidirectional"))
    )
    (net (code "150") (name "unconnected-(U1D-IO_L33P_M3DQ12_3-PadP2)") (class "Default")
      (node (ref "U1") (pin "P2") (pinfunction "IO_L33P_M3DQ12_3_P2") (pintype "bidirectional"))
    )
    (net (code "151") (name "unconnected-(U1D-IO_L34N_M3UDQSN_3-PadN1)") (class "Default")
      (node (ref "U1") (pin "N1") (pinfunction "IO_L34N_M3UDQSN_3_N1") (pintype "bidirectional"))
    )
    (net (code "152") (name "unconnected-(U1D-IO_L34P_M3UDQS_3-PadN3)") (class "Default")
      (node (ref "U1") (pin "N3") (pinfunction "IO_L34P_M3UDQS_3_N3") (pintype "bidirectional"))
    )
    (net (code "153") (name "unconnected-(U1D-IO_L35N_M3DQ11_3-PadM1)") (class "Default")
      (node (ref "U1") (pin "M1") (pinfunction "IO_L35N_M3DQ11_3_M1") (pintype "bidirectional"))
    )
    (net (code "154") (name "unconnected-(U1D-IO_L35P_M3DQ10_3-PadM2)") (class "Default")
      (node (ref "U1") (pin "M2") (pinfunction "IO_L35P_M3DQ10_3_M2") (pintype "bidirectional"))
    )
    (net (code "155") (name "unconnected-(U1D-IO_L36N_M3DQ9_3-PadL1)") (class "Default")
      (node (ref "U1") (pin "L1") (pinfunction "IO_L36N_M3DQ9_3_L1") (pintype "bidirectional"))
    )
    (net (code "156") (name "unconnected-(U1D-IO_L36P_M3DQ8_3-PadL3)") (class "Default")
      (node (ref "U1") (pin "L3") (pinfunction "IO_L36P_M3DQ8_3_L3") (pintype "bidirectional"))
    )
    (net (code "157") (name "unconnected-(U1D-IO_L37N_M3DQ1_3-PadK1)") (class "Default")
      (node (ref "U1") (pin "K1") (pinfunction "IO_L37N_M3DQ1_3_K1") (pintype "bidirectional"))
    )
    (net (code "158") (name "unconnected-(U1D-IO_L37P_M3DQ0_3-PadK2)") (class "Default")
      (node (ref "U1") (pin "K2") (pinfunction "IO_L37P_M3DQ0_3_K2") (pintype "bidirectional"))
    )
    (net (code "159") (name "unconnected-(U1D-IO_L38N_M3DQ3_3-PadJ1)") (class "Default")
      (node (ref "U1") (pin "J1") (pinfunction "IO_L38N_M3DQ3_3_J1") (pintype "bidirectional"))
    )
    (net (code "160") (name "unconnected-(U1D-IO_L38P_M3DQ2_3-PadJ3)") (class "Default")
      (node (ref "U1") (pin "J3") (pinfunction "IO_L38P_M3DQ2_3_J3") (pintype "bidirectional"))
    )
    (net (code "161") (name "unconnected-(U1D-IO_L39N_M3LDQSN_3-PadH1)") (class "Default")
      (node (ref "U1") (pin "H1") (pinfunction "IO_L39N_M3LDQSN_3_H1") (pintype "bidirectional"))
    )
    (net (code "162") (name "unconnected-(U1D-IO_L39P_M3LDQS_3-PadH2)") (class "Default")
      (node (ref "U1") (pin "H2") (pinfunction "IO_L39P_M3LDQS_3_H2") (pintype "bidirectional"))
    )
    (net (code "163") (name "unconnected-(U1D-IO_L40N_M3DQ7_3-PadG1)") (class "Default")
      (node (ref "U1") (pin "G1") (pinfunction "IO_L40N_M3DQ7_3_G1") (pintype "bidirectional"))
    )
    (net (code "164") (name "unconnected-(U1D-IO_L40P_M3DQ6_3-PadG3)") (class "Default")
      (node (ref "U1") (pin "G3") (pinfunction "IO_L40P_M3DQ6_3_G3") (pintype "bidirectional"))
    )
    (net (code "165") (name "unconnected-(U1D-IO_L41N_GCLK26_M3DQ5_3-PadF1)") (class "Default")
      (node (ref "U1") (pin "F1") (pinfunction "IO_L41N_GCLK26_M3DQ5_3_F1") (pintype "bidirectional"))
    )
    (net (code "166") (name "unconnected-(U1D-IO_L41P_GCLK27_M3DQ4_3-PadF2)") (class "Default")
      (node (ref "U1") (pin "F2") (pinfunction "IO_L41P_GCLK27_M3DQ4_3_F2") (pintype "bidirectional"))
    )
    (net (code "167") (name "unconnected-(U1D-IO_L42N_GCLK24_M3LDM_3-PadJ4)") (class "Default")
      (node (ref "U1") (pin "J4") (pinfunction "IO_L42N_GCLK24_M3LDM_3_J4") (pintype "bidirectional"))
    )
    (net (code "168") (name "unconnected-(U1D-IO_L42P_GCLK25_TRDY2_M3UDM_3-PadK3)") (class "Default")
      (node (ref "U1") (pin "K3") (pinfunction "IO_L42P_GCLK25_TRDY2_M3UDM_3_K3") (pintype "bidirectional"))
    )
    (net (code "169") (name "unconnected-(U1D-IO_L43N_GCLK22_IRDY2_M3CASN_3-PadH5)") (class "Default")
      (node (ref "U1") (pin "H5") (pinfunction "IO_L43N_GCLK22_IRDY2_M3CASN_3_H5") (pintype "bidirectional"))
    )
    (net (code "170") (name "unconnected-(U1D-IO_L43P_GCLK23_M3RASN_3-PadJ6)") (class "Default")
      (node (ref "U1") (pin "J6") (pinfunction "IO_L43P_GCLK23_M3RASN_3_J6") (pintype "bidirectional"))
    )
    (net (code "171") (name "unconnected-(U1D-IO_L44N_GCLK20_M3A6_3-PadH3)") (class "Default")
      (node (ref "U1") (pin "H3") (pinfunction "IO_L44N_GCLK20_M3A6_3_H3") (pintype "bidirectional"))
    )
    (net (code "172") (name "unconnected-(U1D-IO_L44P_GCLK21_M3A5_3-PadH4)") (class "Default")
      (node (ref "U1") (pin "H4") (pinfunction "IO_L44P_GCLK21_M3A5_3_H4") (pintype "bidirectional"))
    )
    (net (code "173") (name "unconnected-(U1D-IO_L45N_M3ODT_3-PadL5)") (class "Default")
      (node (ref "U1") (pin "L5") (pinfunction "IO_L45N_M3ODT_3_L5") (pintype "bidirectional"))
    )
    (net (code "174") (name "unconnected-(U1D-IO_L45P_M3A3_3-PadL4)") (class "Default")
      (node (ref "U1") (pin "L4") (pinfunction "IO_L45P_M3A3_3_L4") (pintype "bidirectional"))
    )
    (net (code "175") (name "unconnected-(U1D-IO_L46N_M3CLKN_3-PadE1)") (class "Default")
      (node (ref "U1") (pin "E1") (pinfunction "IO_L46N_M3CLKN_3_E1") (pintype "bidirectional"))
    )
    (net (code "176") (name "unconnected-(U1D-IO_L46P_M3CLK_3-PadE2)") (class "Default")
      (node (ref "U1") (pin "E2") (pinfunction "IO_L46P_M3CLK_3_E2") (pintype "bidirectional"))
    )
    (net (code "177") (name "unconnected-(U1D-IO_L47N_M3A1_3-PadK6)") (class "Default")
      (node (ref "U1") (pin "K6") (pinfunction "IO_L47N_M3A1_3_K6") (pintype "bidirectional"))
    )
    (net (code "178") (name "unconnected-(U1D-IO_L47P_M3A0_3-PadK5)") (class "Default")
      (node (ref "U1") (pin "K5") (pinfunction "IO_L47P_M3A0_3_K5") (pintype "bidirectional"))
    )
    (net (code "179") (name "unconnected-(U1D-IO_L48N_M3BA1_3-PadC2)") (class "Default")
      (node (ref "U1") (pin "C2") (pinfunction "IO_L48N_M3BA1_3_C2") (pintype "bidirectional"))
    )
    (net (code "180") (name "unconnected-(U1D-IO_L48P_M3BA0_3-PadC3)") (class "Default")
      (node (ref "U1") (pin "C3") (pinfunction "IO_L48P_M3BA0_3_C3") (pintype "bidirectional"))
    )
    (net (code "181") (name "unconnected-(U1D-IO_L49N_M3A2_3-PadD1)") (class "Default")
      (node (ref "U1") (pin "D1") (pinfunction "IO_L49N_M3A2_3_D1") (pintype "bidirectional"))
    )
    (net (code "182") (name "unconnected-(U1D-IO_L49P_M3A7_3-PadD3)") (class "Default")
      (node (ref "U1") (pin "D3") (pinfunction "IO_L49P_M3A7_3_D3") (pintype "bidirectional"))
    )
    (net (code "183") (name "unconnected-(U1D-IO_L50N_M3BA2_3-PadB1)") (class "Default")
      (node (ref "U1") (pin "B1") (pinfunction "IO_L50N_M3BA2_3_B1") (pintype "bidirectional"))
    )
    (net (code "184") (name "unconnected-(U1D-IO_L50P_M3WE_3-PadC1)") (class "Default")
      (node (ref "U1") (pin "C1") (pinfunction "IO_L50P_M3WE_3_C1") (pintype "bidirectional"))
    )
    (net (code "185") (name "unconnected-(U1D-IO_L51N_M3A4_3-PadG5)") (class "Default")
      (node (ref "U1") (pin "G5") (pinfunction "IO_L51N_M3A4_3_G5") (pintype "bidirectional"))
    )
    (net (code "186") (name "unconnected-(U1D-IO_L51P_M3A10_3-PadG6)") (class "Default")
      (node (ref "U1") (pin "G6") (pinfunction "IO_L51P_M3A10_3_G6") (pintype "bidirectional"))
    )
    (net (code "187") (name "unconnected-(U1D-IO_L52N_M3A9_3-PadA2)") (class "Default")
      (node (ref "U1") (pin "A2") (pinfunction "IO_L52N_M3A9_3_A2") (pintype "bidirectional"))
    )
    (net (code "188") (name "unconnected-(U1D-IO_L52P_M3A8_3-PadB2)") (class "Default")
      (node (ref "U1") (pin "B2") (pinfunction "IO_L52P_M3A8_3_B2") (pintype "bidirectional"))
    )
    (net (code "189") (name "unconnected-(U1D-IO_L53N_M3A12_3-PadF3)") (class "Default")
      (node (ref "U1") (pin "F3") (pinfunction "IO_L53N_M3A12_3_F3") (pintype "bidirectional"))
    )
    (net (code "190") (name "unconnected-(U1D-IO_L53P_M3CKE_3-PadF4)") (class "Default")
      (node (ref "U1") (pin "F4") (pinfunction "IO_L53P_M3CKE_3_F4") (pintype "bidirectional"))
    )
    (net (code "191") (name "unconnected-(U1D-IO_L54N_M3A11_3-PadE3)") (class "Default")
      (node (ref "U1") (pin "E3") (pinfunction "IO_L54N_M3A11_3_E3") (pintype "bidirectional"))
    )
    (net (code "192") (name "unconnected-(U1D-IO_L54P_M3RESET_3-PadE4)") (class "Default")
      (node (ref "U1") (pin "E4") (pinfunction "IO_L54P_M3RESET_3_E4") (pintype "bidirectional"))
    )
    (net (code "193") (name "unconnected-(U1D-IO_L55N_M3A14_3-PadF5)") (class "Default")
      (node (ref "U1") (pin "F5") (pinfunction "IO_L55N_M3A14_3_F5") (pintype "bidirectional"))
    )
    (net (code "194") (name "unconnected-(U1D-IO_L55P_M3A13_3-PadF6)") (class "Default")
      (node (ref "U1") (pin "F6") (pinfunction "IO_L55P_M3A13_3_F6") (pintype "bidirectional"))
    )
    (net (code "195") (name "unconnected-(U1D-IO_L83N_VREF_3-PadA3)") (class "Default")
      (node (ref "U1") (pin "A3") (pinfunction "IO_L83N_VREF_3_A3") (pintype "bidirectional"))
    )
    (net (code "196") (name "unconnected-(U1D-IO_L83P_3-PadB3)") (class "Default")
      (node (ref "U1") (pin "B3") (pinfunction "IO_L83P_3_B3") (pintype "bidirectional"))
    )
    (net (code "197") (name "unconnected-(U1E-CMPCS_B_2-PadL11)") (class "Default")
      (node (ref "U1") (pin "L11") (pinfunction "CMPCS_B_2_L11") (pintype "input"))
    )
    (net (code "198") (name "unconnected-(U1E-DONE_2-PadP13)") (class "Default")
      (node (ref "U1") (pin "P13") (pinfunction "DONE_2_P13") (pintype "bidirectional"))
    )
    (net (code "199") (name "unconnected-(U1E-PROGRAM_B_2-PadT2)") (class "Default")
      (node (ref "U1") (pin "T2") (pinfunction "PROGRAM_B_2_T2") (pintype "input"))
    )
    (net (code "200") (name "unconnected-(U1E-SUSPEND-PadP14)") (class "Default")
      (node (ref "U1") (pin "P14") (pinfunction "SUSPEND_P14") (pintype "input"))
    )
    (net (code "201") (name "unconnected-(U1E-TCK-PadC14)") (class "Default")
      (node (ref "U1") (pin "C14") (pinfunction "TCK_C14") (pintype "input"))
    )
    (net (code "202") (name "unconnected-(U1E-TDI-PadC12)") (class "Default")
      (node (ref "U1") (pin "C12") (pinfunction "TDI_C12") (pintype "input"))
    )
    (net (code "203") (name "unconnected-(U1E-TDO-PadE14)") (class "Default")
      (node (ref "U1") (pin "E14") (pinfunction "TDO_E14") (pintype "output"))
    )
    (net (code "204") (name "unconnected-(U1E-TMS-PadA15)") (class "Default")
      (node (ref "U1") (pin "A15") (pinfunction "TMS_A15") (pintype "input"))
    )
    (net (code "205") (name "unconnected-(U2-RDQS#-PadA2)") (class "Default")
      (node (ref "U2") (pin "A2") (pinfunction "RDQS#_A2") (pintype "bidirectional"))
    )
    (net (code "206") (name "unconnected-(U2-VREF-PadE2)") (class "Default")
      (node (ref "U2") (pin "E2") (pinfunction "VREF_E2") (pintype "power_in"))
    )
  )
)
